# Selection_1.net
KiCad netlist of a schematic drawn in Altium Designer
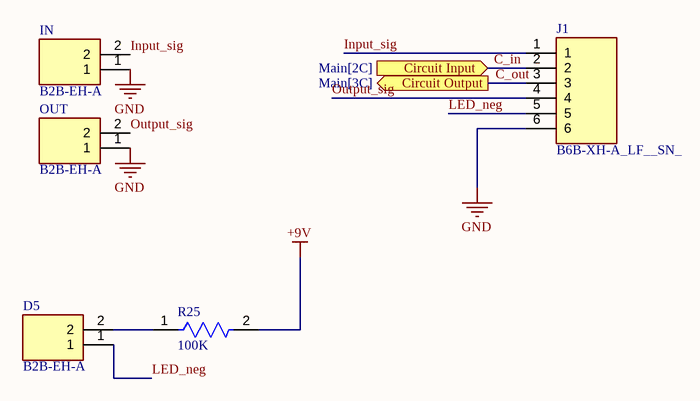
[diagram p0: Selection_1.SchDoc]

(export (version "E")
  (design (tool "Eeschema 10.0.6"))
  (components
    (comp (ref "D5")
      (value "B2B-EH-A")
      (footprint "SamacSys:SHDR2W64P0X250_1X2_750X380X600P")
      (description "Connector")
      (libsource (lib "SamacSys") (part "B2B-EH-A"))
    )
    (comp (ref "IN")
      (value "B2B-EH-A")
      (footprint "SamacSys:SHDR2W64P0X250_1X2_750X380X600P")
      (description "Connector")
      (libsource (lib "SamacSys") (part "B2B-EH-A"))
    )
    (comp (ref "J1")
      (value "B6B-XH-A_LF__SN_")
      (footprint "SamacSys:SHDR6W64P0X250_1X6_1740X575X700P")
      (description "Connector")
      (fields
        (field (name "MANUFACTURER_PART_NUMBER") "B6B-XH-A(LF)(SN)")
        (field (name "MOUSER PART NUMBER") "306-B6BXHALFSN")
      )
      (libsource (lib "*") (part "B6B-XH-A_LF__SN_"))
    )
    (comp (ref "OUT")
      (value "B2B-EH-A")
      (footprint "SamacSys:SHDR2W64P0X250_1X2_750X380X600P")
      (description "Connector")
      (libsource (lib "SamacSys") (part "B2B-EH-A"))
    )
    (comp (ref "R25")
      (value "100K")
      (footprint "FP-MRS1600-MFG")
      (description "RES 20K OHM 0.4W 1% AXIAL")
      (fields (field (name "TOLERANCE") "1%"))
      (libsource (lib "Altium Content Vault") (part "1029c3af85768c4190bb7ad29bc67b5"))
    )
  )
  (nets
    (net (code "1") (name "+9V") (class "Default")
      (node (ref "R25") (pin "2") (pinfunction "2_2") (pintype "passive"))
    )
    (net (code "2") (name "/C_in") (class "Default")
      (node (ref "J1") (pin "2") (pinfunction "2_2") (pintype "passive"))
    )
    (net (code "3") (name "/C_out") (class "Default")
      (node (ref "J1") (pin "3") (pinfunction "3_3") (pintype "passive"))
    )
    (net (code "4") (name "/Input_sig") (class "Default")
      (node (ref "IN") (pin "2") (pinfunction "2_2") (pintype "passive"))
      (node (ref "J1") (pin "1") (pinfunction "1_1") (pintype "passive"))
    )
    (net (code "5") (name "/LED_neg") (class "Default")
      (node (ref "D5") (pin "1") (pinfunction "1_1") (pintype "passive"))
      (node (ref "J1") (pin "5") (pinfunction "5_5") (pintype "passive"))
    )
    (net (code "6") (name "/Output_sig") (class "Default")
      (node (ref "J1") (pin "4") (pinfunction "4_4") (pintype "passive"))
      (node (ref "OUT") (pin "2") (pinfunction "2_2") (pintype "passive"))
    )
    (net (code "7") (name "GND") (class "Default")
      (node (ref "IN") (pin "1") (pinfunction "1_1") (pintype "passive"))
      (node (ref "J1") (pin "6") (pinfunction "6_6") (pintype "passive"))
      (node (ref "OUT") (pin "1") (pinfunction "1_1") (pintype "passive"))
    )
    (net (code "8") (name "Net-(D5-Pad2)") (class "Default")
      (node (ref "D5") (pin "2") (pinfunction "2_2") (pintype "passive"))
      (node (ref "R25") (pin "1") (pinfunction "1_1") (pintype "passive"))
    )
  )
)
